# 1.net
KiCad netlist of a schematic drawn in Altium Designer
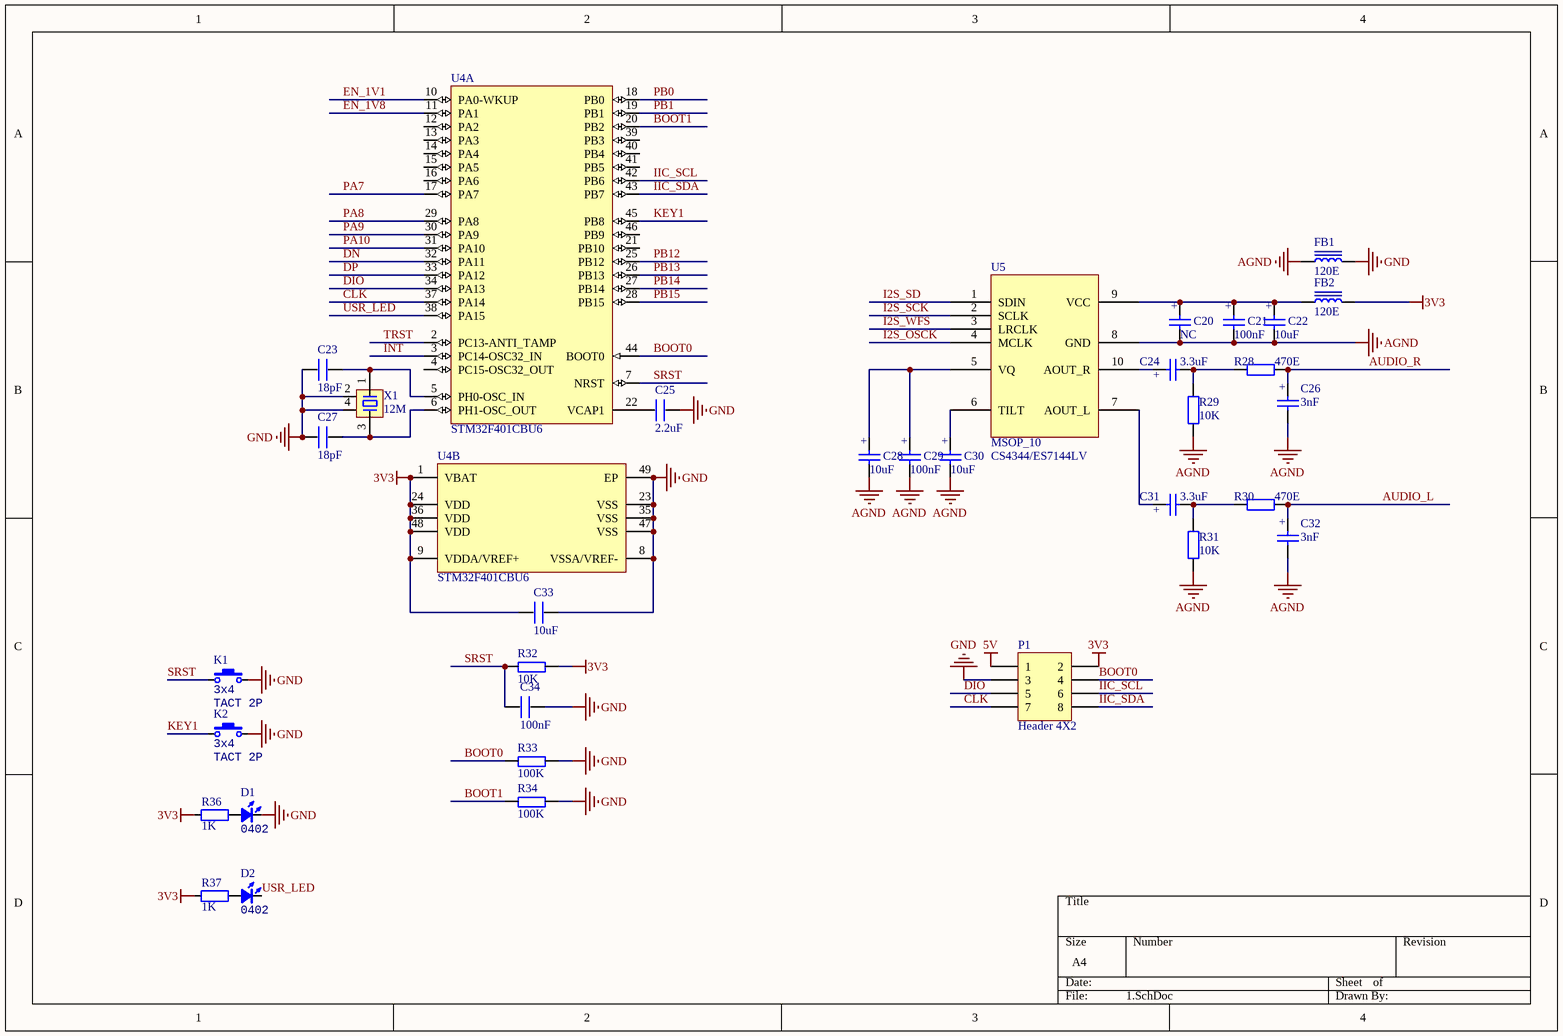
[diagram p0: 1.SchDoc]

(export (version "E")
  (design (tool "Eeschema 10.0.6"))
  (components
    (comp (ref "C20")
      (value "NC")
      (footprint "0603_CAP")
      (description "电容")
      (fields (field (name "Comment") "0402") (field (name "PUBLISHER") "Altium Limited"))
      (libsource (lib "Fxfly") (part "Cap"))
    )
    (comp (ref "C21")
      (value "100nF")
      (footprint "0603_CAP")
      (description "电容")
      (fields (field (name "Comment") "0402") (field (name "PUBLISHER") "Altium Limited"))
      (libsource (lib "Fxfly") (part "Cap"))
    )
    (comp (ref "C22")
      (value "10uF")
      (footprint "0603_CAP")
      (description "电容")
      (fields (field (name "Comment") "0603") (field (name "PUBLISHER") "Altium Limited"))
      (libsource (lib "Fxfly") (part "Cap"))
    )
    (comp (ref "C23") (value "18pF") (footprint "0603_CAP") (libsource (lib "阿波罗STM32F4&F7底板封装库") (part "C")))
    (comp (ref "C24")
      (value "3.3uF")
      (footprint "0603_CAP")
      (description "电容")
      (fields (field (name "Comment") "1206") (field (name "PUBLISHER") "Altium Limited"))
      (libsource (lib "Fxfly") (part "Cap"))
    )
    (comp (ref "C25")
      (value "2.2uF")
      (footprint "0603_CAP")
      (libsource (lib "阿波罗STM32F4&F7底板封装库") (part "C"))
    )
    (comp (ref "C26")
      (value "3nF")
      (footprint "0603_CAP")
      (description "电容")
      (fields (field (name "Comment") "0603") (field (name "PUBLISHER") "Altium Limited"))
      (libsource (lib "Fxfly") (part "Cap"))
    )
    (comp (ref "C27") (value "18pF") (footprint "0603_CAP") (libsource (lib "阿波罗STM32F4&F7底板封装库") (part "C")))
    (comp (ref "C28")
      (value "10uF")
      (footprint "0603_CAP")
      (description "电容")
      (fields (field (name "Comment") "0603") (field (name "PUBLISHER") "Altium Limited"))
      (libsource (lib "Fxfly") (part "Cap"))
    )
    (comp (ref "C29")
      (value "100nF")
      (footprint "0603_CAP")
      (description "电容")
      (fields (field (name "Comment") "0402") (field (name "PUBLISHER") "Altium Limited"))
      (libsource (lib "Fxfly") (part "Cap"))
    )
    (comp (ref "C30")
      (value "10uF")
      (footprint "0603_CAP")
      (description "电容")
      (fields (field (name "Comment") "0603") (field (name "PUBLISHER") "Altium Limited"))
      (libsource (lib "Fxfly") (part "Cap"))
    )
    (comp (ref "C31")
      (value "3.3uF")
      (footprint "0603_CAP")
      (description "电容")
      (fields (field (name "Comment") "1206") (field (name "PUBLISHER") "Altium Limited"))
      (libsource (lib "Fxfly") (part "Cap"))
    )
    (comp (ref "C32")
      (value "3nF")
      (footprint "0603_CAP")
      (description "电容")
      (fields (field (name "Comment") "0603") (field (name "PUBLISHER") "Altium Limited"))
      (libsource (lib "Fxfly") (part "Cap"))
    )
    (comp (ref "C33") (value "10uF") (footprint "0603_CAP") (libsource (lib "阿波罗STM32F4&F7底板封装库") (part "C")))
    (comp (ref "C34")
      (value "100nF")
      (footprint "0603_CAP")
      (libsource (lib "阿波罗STM32F4&F7底板封装库") (part "C"))
    )
    (comp (ref "D1")
      (value "color?")
      (footprint "SMDLED-0603")
      (description "LED")
      (fields (field (name "TYPE") "0402"))
      (libsource (lib "KitSprout") (part "LED_0402"))
    )
    (comp (ref "D2")
      (value "color?")
      (footprint "SMDLED-0603")
      (description "LED")
      (fields (field (name "TYPE") "0402"))
      (libsource (lib "KitSprout") (part "LED_0402"))
    )
    (comp (ref "FB1")
      (value "120E")
      (footprint "2520-L")
      (description "磁珠")
      (fields (field (name "Comment") "0603") (field (name "PUBLISHER") "Altium Limited"))
      (libsource (lib "Fxfly") (part "FB"))
    )
    (comp (ref "FB2")
      (value "120E")
      (footprint "2520-L")
      (description "磁珠")
      (fields (field (name "Comment") "0603") (field (name "PUBLISHER") "Altium Limited"))
      (libsource (lib "Fxfly") (part "FB"))
    )
    (comp (ref "K1")
      (value "3x4")
      (footprint "ButtonTACT_3x4x2_180H")
      (description "Button")
      (fields (field (name "TYPE") "TACT 2P") (field (name "Comment") "TACT 2P"))
      (libsource (lib "KitSprout") (part "ButtonTACT_3x4x2_180"))
    )
    (comp (ref "K2")
      (value "3x4")
      (footprint "ButtonTACT_3x4x2_180H")
      (description "Button")
      (fields (field (name "TYPE") "TACT 2P") (field (name "Comment") "TACT 2P"))
      (libsource (lib "KitSprout") (part "ButtonTACT_3x4x2_180"))
    )
    (comp (ref "P1")
      (value "Header 4X2")
      (footprint "HDR2X4")
      (description "Header, 4-Pin, Dual row")
      (fields (field (name "PUBLISHER") "Altium Limited"))
      (libsource (lib "Miscellaneous Connectors") (part "Header 4X2"))
    )
    (comp (ref "R28")
      (value "470E")
      (footprint "0603_RES")
      (description "电阻")
      (fields (field (name "Comment") "0603") (field (name "PUBLISHER") "Altium Limited"))
      (libsource (lib "Fxfly") (part "R"))
    )
    (comp (ref "R29")
      (value "10K")
      (footprint "0603_RES")
      (description "电阻")
      (fields (field (name "Comment") "0402") (field (name "PUBLISHER") "Altium Limited"))
      (libsource (lib "") (part "R_1"))
    )
    (comp (ref "R30")
      (value "470E")
      (footprint "0603_RES")
      (description "电阻")
      (fields (field (name "Comment") "0603") (field (name "PUBLISHER") "Altium Limited"))
      (libsource (lib "Fxfly") (part "R"))
    )
    (comp (ref "R31")
      (value "10K")
      (footprint "0603_RES")
      (description "电阻")
      (fields (field (name "Comment") "0402") (field (name "PUBLISHER") "Altium Limited"))
      (libsource (lib "") (part "R_1"))
    )
    (comp (ref "R32") (value "10K") (footprint "0603_RES") (libsource (lib "STM32F429核心板封装库") (part "R")))
    (comp (ref "R33") (value "100K") (footprint "0603_RES") (libsource (lib "STM32F429核心板封装库") (part "R")))
    (comp (ref "R34") (value "100K") (footprint "0603_RES") (libsource (lib "STM32F429核心板封装库") (part "R")))
    (comp (ref "R36")
      (value "1K")
      (footprint "0603_RES")
      (description "Resistor")
      (libsource (lib "MyPcbLib") (part "电阻-0402"))
    )
    (comp (ref "R37")
      (value "1K")
      (footprint "0603_RES")
      (description "Resistor")
      (libsource (lib "MyPcbLib") (part "电阻-0402"))
    )
    (comp (ref "U4")
      (value "STM32F401CBU6")
      (footprint "401cb")
      (fields (field (name "MANUFACTURER") "STMicroelectronics"))
      (libsource (lib "STMicroelectronics STM32 F4") (part "STM32F401CBU6"))
    )
    (comp (ref "U5")
      (value "MSOP_10")
      (footprint "TSSOP-10_L3.0-W3.0-P0.50-LS4.9-BL")
      (description "DAC")
      (fields (field (name "ALTIUM_VALUE") "CS4344/ES7144LV"))
      (libsource (lib "Fxfly") (part "CS4344"))
    )
    (comp (ref "X1")
      (value "12M")
      (footprint "XTAL3225")
      (description "4脚无源晶振")
      (fields (field (name "版权归属") "源创客"))
      (libsource (lib "10.1 - 保险丝-晶振") (part "XTAL-4P"))
    )
  )
  (nets
    (net (code "1") (name "/AUDIO_L") (class "Default")
      (node (ref "C32") (pin "1") (pinfunction "+_1") (pintype "passive"))
      (node (ref "R30") (pin "1") (pinfunction "1_1") (pintype "passive"))
    )
    (net (code "2") (name "/AUDIO_R") (class "Default")
      (node (ref "C26") (pin "1") (pinfunction "+_1") (pintype "passive"))
      (node (ref "R28") (pin "1") (pinfunction "1_1") (pintype "passive"))
    )
    (net (code "3") (name "/BOOT0") (class "Default")
      (node (ref "P1") (pin "4") (pinfunction "4_4") (pintype "passive"))
      (node (ref "R33") (pin "1") (pintype "passive"))
      (node (ref "U4") (pin "44") (pinfunction "BOOT0_44") (pintype "input"))
    )
    (net (code "4") (name "/BOOT1") (class "Default")
      (node (ref "R34") (pin "1") (pintype "passive"))
      (node (ref "U4") (pin "20") (pinfunction "PB2_20") (pintype "bidirectional"))
    )
    (net (code "5") (name "/CLK") (class "Default")
      (node (ref "P1") (pin "7") (pinfunction "7_7") (pintype "passive"))
      (node (ref "U4") (pin "37") (pinfunction "PA14_37") (pintype "bidirectional"))
    )
    (net (code "6") (name "/DIO") (class "Default")
      (node (ref "P1") (pin "5") (pinfunction "5_5") (pintype "passive"))
      (node (ref "U4") (pin "34") (pinfunction "PA13_34") (pintype "bidirectional"))
    )
    (net (code "7") (name "/DN") (class "Default")
      (node (ref "U4") (pin "32") (pinfunction "PA11_32") (pintype "bidirectional"))
    )
    (net (code "8") (name "/DP") (class "Default")
      (node (ref "U4") (pin "33") (pinfunction "PA12_33") (pintype "bidirectional"))
    )
    (net (code "9") (name "/EN_1V1") (class "Default")
      (node (ref "U4") (pin "10") (pinfunction "PA0-WKUP_10") (pintype "bidirectional"))
    )
    (net (code "10") (name "/EN_1V8") (class "Default")
      (node (ref "U4") (pin "11") (pinfunction "PA1_11") (pintype "bidirectional"))
    )
    (net (code "11") (name "/I2S_OSCK") (class "Default")
      (node (ref "U5") (pin "4") (pinfunction "MCLK_4") (pintype "passive"))
    )
    (net (code "12") (name "/I2S_SCK") (class "Default")
      (node (ref "U5") (pin "2") (pinfunction "SCLK_2") (pintype "passive"))
    )
    (net (code "13") (name "/I2S_SD") (class "Default")
      (node (ref "U5") (pin "1") (pinfunction "SDIN_1") (pintype "passive"))
    )
    (net (code "14") (name "/I2S_WFS") (class "Default")
      (node (ref "U5") (pin "3") (pinfunction "LRCLK_3") (pintype "passive"))
    )
    (net (code "15") (name "/IIC_SCL") (class "Default")
      (node (ref "P1") (pin "6") (pinfunction "6_6") (pintype "passive"))
      (node (ref "U4") (pin "42") (pinfunction "PB6_42") (pintype "bidirectional"))
    )
    (net (code "16") (name "/IIC_SDA") (class "Default")
      (node (ref "P1") (pin "8") (pinfunction "8_8") (pintype "passive"))
      (node (ref "U4") (pin "43") (pinfunction "PB7_43") (pintype "bidirectional"))
    )
    (net (code "17") (name "/INT") (class "Default")
      (node (ref "U4") (pin "3") (pinfunction "PC14-OSC32_IN_3") (pintype "bidirectional"))
    )
    (net (code "18") (name "/KEY1") (class "Default")
      (node (ref "K2") (pin "1") (pinfunction "1_1") (pintype "passive"))
      (node (ref "U4") (pin "45") (pinfunction "PB8_45") (pintype "bidirectional"))
    )
    (net (code "19") (name "/PA7") (class "Default")
      (node (ref "U4") (pin "17") (pinfunction "PA7_17") (pintype "bidirectional"))
    )
    (net (code "20") (name "/PA8") (class "Default")
      (node (ref "U4") (pin "29") (pinfunction "PA8_29") (pintype "bidirectional"))
    )
    (net (code "21") (name "/PA9") (class "Default")
      (node (ref "U4") (pin "30") (pinfunction "PA9_30") (pintype "bidirectional"))
    )
    (net (code "22") (name "/PA10") (class "Default")
      (node (ref "U4") (pin "31") (pinfunction "PA10_31") (pintype "bidirectional"))
    )
    (net (code "23") (name "/PB0") (class "Default")
      (node (ref "U4") (pin "18") (pinfunction "PB0_18") (pintype "bidirectional"))
    )
    (net (code "24") (name "/PB1") (class "Default")
      (node (ref "U4") (pin "19") (pinfunction "PB1_19") (pintype "bidirectional"))
    )
    (net (code "25") (name "/PB12") (class "Default")
      (node (ref "U4") (pin "25") (pinfunction "PB12_25") (pintype "bidirectional"))
    )
    (net (code "26") (name "/PB13") (class "Default")
      (node (ref "U4") (pin "26") (pinfunction "PB13_26") (pintype "bidirectional"))
    )
    (net (code "27") (name "/PB14") (class "Default")
      (node (ref "U4") (pin "27") (pinfunction "PB14_27") (pintype "bidirectional"))
    )
    (net (code "28") (name "/PB15") (class "Default")
      (node (ref "U4") (pin "28") (pinfunction "PB15_28") (pintype "bidirectional"))
    )
    (net (code "29") (name "/SRST") (class "Default")
      (node (ref "C34") (pin "2") (pintype "passive"))
      (node (ref "K1") (pin "1") (pinfunction "1_1") (pintype "passive"))
      (node (ref "R32") (pin "1") (pintype "passive"))
      (node (ref "U4") (pin "7") (pinfunction "NRST_7") (pintype "bidirectional"))
    )
    (net (code "30") (name "/TRST") (class "Default")
      (node (ref "U4") (pin "2") (pinfunction "PC13-ANTI_TAMP_2") (pintype "bidirectional"))
    )
    (net (code "31") (name "/USR_LED") (class "Default")
      (node (ref "D2") (pin "2") (pinfunction "K_2") (pintype "passive"))
      (node (ref "U4") (pin "38") (pinfunction "PA15_38") (pintype "bidirectional"))
    )
    (net (code "32") (name "3V3") (class "Default")
      (node (ref "C33") (pin "2") (pintype "passive"))
      (node (ref "FB2") (pin "2") (pinfunction "2_2") (pintype "passive"))
      (node (ref "P1") (pin "2") (pinfunction "2_2") (pintype "passive"))
      (node (ref "R32") (pin "2") (pintype "passive"))
      (node (ref "R36") (pin "1") (pinfunction "1_1") (pintype "passive"))
      (node (ref "R37") (pin "1") (pinfunction "1_1") (pintype "passive"))
      (node (ref "U4") (pin "1") (pinfunction "VBAT_1") (pintype "power_in"))
      (node (ref "U4") (pin "24") (pinfunction "VDD_24") (pintype "power_in"))
      (node (ref "U4") (pin "36") (pinfunction "VDD_36") (pintype "power_in"))
      (node (ref "U4") (pin "48") (pinfunction "VDD_48") (pintype "power_in"))
      (node (ref "U4") (pin "9") (pinfunction "VDDA/VREF+_9") (pintype "power_in"))
    )
    (net (code "33") (name "5V") (class "Default")
      (node (ref "P1") (pin "1") (pinfunction "1_1") (pintype "passive"))
    )
    (net (code "34") (name "AGND") (class "Default")
      (node (ref "C20") (pin "2") (pinfunction "2_2") (pintype "passive"))
      (node (ref "C21") (pin "2") (pinfunction "2_2") (pintype "passive"))
      (node (ref "C22") (pin "2") (pinfunction "2_2") (pintype "passive"))
      (node (ref "C26") (pin "2") (pinfunction "2_2") (pintype "passive"))
      (node (ref "C28") (pin "2") (pinfunction "2_2") (pintype "passive"))
      (node (ref "C29") (pin "2") (pinfunction "2_2") (pintype "passive"))
      (node (ref "C30") (pin "2") (pinfunction "2_2") (pintype "passive"))
      (node (ref "C32") (pin "2") (pinfunction "2_2") (pintype "passive"))
      (node (ref "FB1") (pin "1") (pinfunction "1_1") (pintype "passive"))
      (node (ref "R29") (pin "1") (pinfunction "1_1") (pintype "passive"))
      (node (ref "R31") (pin "1") (pinfunction "1_1") (pintype "passive"))
      (node (ref "U5") (pin "8") (pinfunction "GND_8") (pintype "passive"))
    )
    (net (code "35") (name "GND") (class "Default")
      (node (ref "C23") (pin "2") (pintype "passive"))
      (node (ref "C25") (pin "1") (pintype "passive"))
      (node (ref "C27") (pin "2") (pintype "passive"))
      (node (ref "C33") (pin "1") (pintype "passive"))
      (node (ref "C34") (pin "1") (pintype "passive"))
      (node (ref "D1") (pin "2") (pinfunction "K_2") (pintype "passive"))
      (node (ref "FB1") (pin "2") (pinfunction "2_2") (pintype "passive"))
      (node (ref "K1") (pin "2") (pinfunction "2_2") (pintype "passive"))
      (node (ref "K2") (pin "2") (pinfunction "2_2") (pintype "passive"))
      (node (ref "P1") (pin "3") (pinfunction "3_3") (pintype "passive"))
      (node (ref "R33") (pin "2") (pintype "passive"))
      (node (ref "R34") (pin "2") (pintype "passive"))
      (node (ref "U4") (pin "23") (pinfunction "VSS_23") (pintype "power_in"))
      (node (ref "U4") (pin "35") (pinfunction "VSS_35") (pintype "power_in"))
      (node (ref "U4") (pin "47") (pinfunction "VSS_47") (pintype "power_in"))
      (node (ref "U4") (pin "49") (pinfunction "EP_49") (pintype "power_in"))
      (node (ref "U4") (pin "8") (pinfunction "VSSA/VREF-_8") (pintype "power_in"))
      (node (ref "X1") (pin "2") (pinfunction "2_2") (pintype "passive"))
      (node (ref "X1") (pin "4") (pinfunction "4_4") (pintype "passive"))
    )
    (net (code "36") (name "Net-(C20-+)") (class "Default")
      (node (ref "C20") (pin "1") (pinfunction "+_1") (pintype "passive"))
      (node (ref "C21") (pin "1") (pinfunction "+_1") (pintype "passive"))
      (node (ref "C22") (pin "1") (pinfunction "+_1") (pintype "passive"))
      (node (ref "FB2") (pin "1") (pinfunction "1_1") (pintype "passive"))
      (node (ref "U5") (pin "9") (pinfunction "VCC_9") (pintype "passive"))
    )
    (net (code "37") (name "Net-(C24-+)") (class "Default")
      (node (ref "C24") (pin "1") (pinfunction "+_1") (pintype "passive"))
      (node (ref "U5") (pin "10") (pinfunction "AOUT_R_10") (pintype "passive"))
    )
    (net (code "38") (name "Net-(C24-Pad2)") (class "Default")
      (node (ref "C24") (pin "2") (pinfunction "2_2") (pintype "passive"))
      (node (ref "R28") (pin "2") (pinfunction "2_2") (pintype "passive"))
      (node (ref "R29") (pin "2") (pinfunction "2_2") (pintype "passive"))
    )
    (net (code "39") (name "Net-(C28-+)") (class "Default")
      (node (ref "C28") (pin "1") (pinfunction "+_1") (pintype "passive"))
      (node (ref "C29") (pin "1") (pinfunction "+_1") (pintype "passive"))
      (node (ref "U5") (pin "5") (pinfunction "VQ_5") (pintype "passive"))
    )
    (net (code "40") (name "Net-(C30-+)") (class "Default")
      (node (ref "C30") (pin "1") (pinfunction "+_1") (pintype "passive"))
      (node (ref "U5") (pin "6") (pinfunction "TILT_6") (pintype "passive"))
    )
    (net (code "41") (name "Net-(C31-+)") (class "Default")
      (node (ref "C31") (pin "1") (pinfunction "+_1") (pintype "passive"))
      (node (ref "U5") (pin "7") (pinfunction "AOUT_L_7") (pintype "passive"))
    )
    (net (code "42") (name "Net-(C31-Pad2)") (class "Default")
      (node (ref "C31") (pin "2") (pinfunction "2_2") (pintype "passive"))
      (node (ref "R30") (pin "2") (pinfunction "2_2") (pintype "passive"))
      (node (ref "R31") (pin "2") (pinfunction "2_2") (pintype "passive"))
    )
    (net (code "43") (name "Net-(D1-A)") (class "Default")
      (node (ref "D1") (pin "1") (pinfunction "A_1") (pintype "passive"))
      (node (ref "R36") (pin "2") (pinfunction "2_2") (pintype "passive"))
    )
    (net (code "44") (name "Net-(D2-A)") (class "Default")
      (node (ref "D2") (pin "1") (pinfunction "A_1") (pintype "passive"))
      (node (ref "R37") (pin "2") (pinfunction "2_2") (pintype "passive"))
    )
    (net (code "45") (name "Net-(U4A-PH0-OSC_IN)") (class "Default")
      (node (ref "C23") (pin "1") (pintype "passive"))
      (node (ref "U4") (pin "5") (pinfunction "PH0-OSC_IN_5") (pintype "bidirectional"))
      (node (ref "X1") (pin "1") (pinfunction "1_1") (pintype "passive"))
    )
    (net (code "46") (name "Net-(U4A-PH1-OSC_OUT)") (class "Default")
      (node (ref "C27") (pin "1") (pintype "passive"))
      (node (ref "U4") (pin "6") (pinfunction "PH1-OSC_OUT_6") (pintype "bidirectional"))
      (node (ref "X1") (pin "3") (pinfunction "3_3") (pintype "passive"))
    )
    (net (code "47") (name "Net-(U4A-VCAP1)") (class "Default")
      (node (ref "C25") (pin "2") (pintype "passive"))
      (node (ref "U4") (pin "22") (pinfunction "VCAP1_22") (pintype "power_in"))
    )
    (net (code "48") (name "unconnected-(U4A-PA2-Pad12)") (class "Default")
      (node (ref "U4") (pin "12") (pinfunction "PA2_12") (pintype "bidirectional"))
    )
    (net (code "49") (name "unconnected-(U4A-PA3-Pad13)") (class "Default")
      (node (ref "U4") (pin "13") (pinfunction "PA3_13") (pintype "bidirectional"))
    )
    (net (code "50") (name "unconnected-(U4A-PA4-Pad14)") (class "Default")
      (node (ref "U4") (pin "14") (pinfunction "PA4_14") (pintype "bidirectional"))
    )
    (net (code "51") (name "unconnected-(U4A-PA5-Pad15)") (class "Default")
      (node (ref "U4") (pin "15") (pinfunction "PA5_15") (pintype "bidirectional"))
    )
    (net (code "52") (name "unconnected-(U4A-PA6-Pad16)") (class "Default")
      (node (ref "U4") (pin "16") (pinfunction "PA6_16") (pintype "bidirectional"))
    )
    (net (code "53") (name "unconnected-(U4A-PB3-Pad39)") (class "Default")
      (node (ref "U4") (pin "39") (pinfunction "PB3_39") (pintype "bidirectional"))
    )
    (net (code "54") (name "unconnected-(U4A-PB4-Pad40)") (class "Default")
      (node (ref "U4") (pin "40") (pinfunction "PB4_40") (pintype "bidirectional"))
    )
    (net (code "55") (name "unconnected-(U4A-PB5-Pad41)") (class "Default")
      (node (ref "U4") (pin "41") (pinfunction "PB5_41") (pintype "bidirectional"))
    )
    (net (code "56") (name "unconnected-(U4A-PB9-Pad46)") (class "Default")
      (node (ref "U4") (pin "46") (pinfunction "PB9_46") (pintype "bidirectional"))
    )
    (net (code "57") (name "unconnected-(U4A-PB10-Pad21)") (class "Default")
      (node (ref "U4") (pin "21") (pinfunction "PB10_21") (pintype "bidirectional"))
    )
    (net (code "58") (name "unconnected-(U4A-PC15-OSC32_OUT-Pad4)") (class "Default")
      (node (ref "U4") (pin "4") (pinfunction "PC15-OSC32_OUT_4") (pintype "bidirectional"))
    )
  )
)
